# CPU.net
KiCad netlist of a schematic drawn in Altium Designer
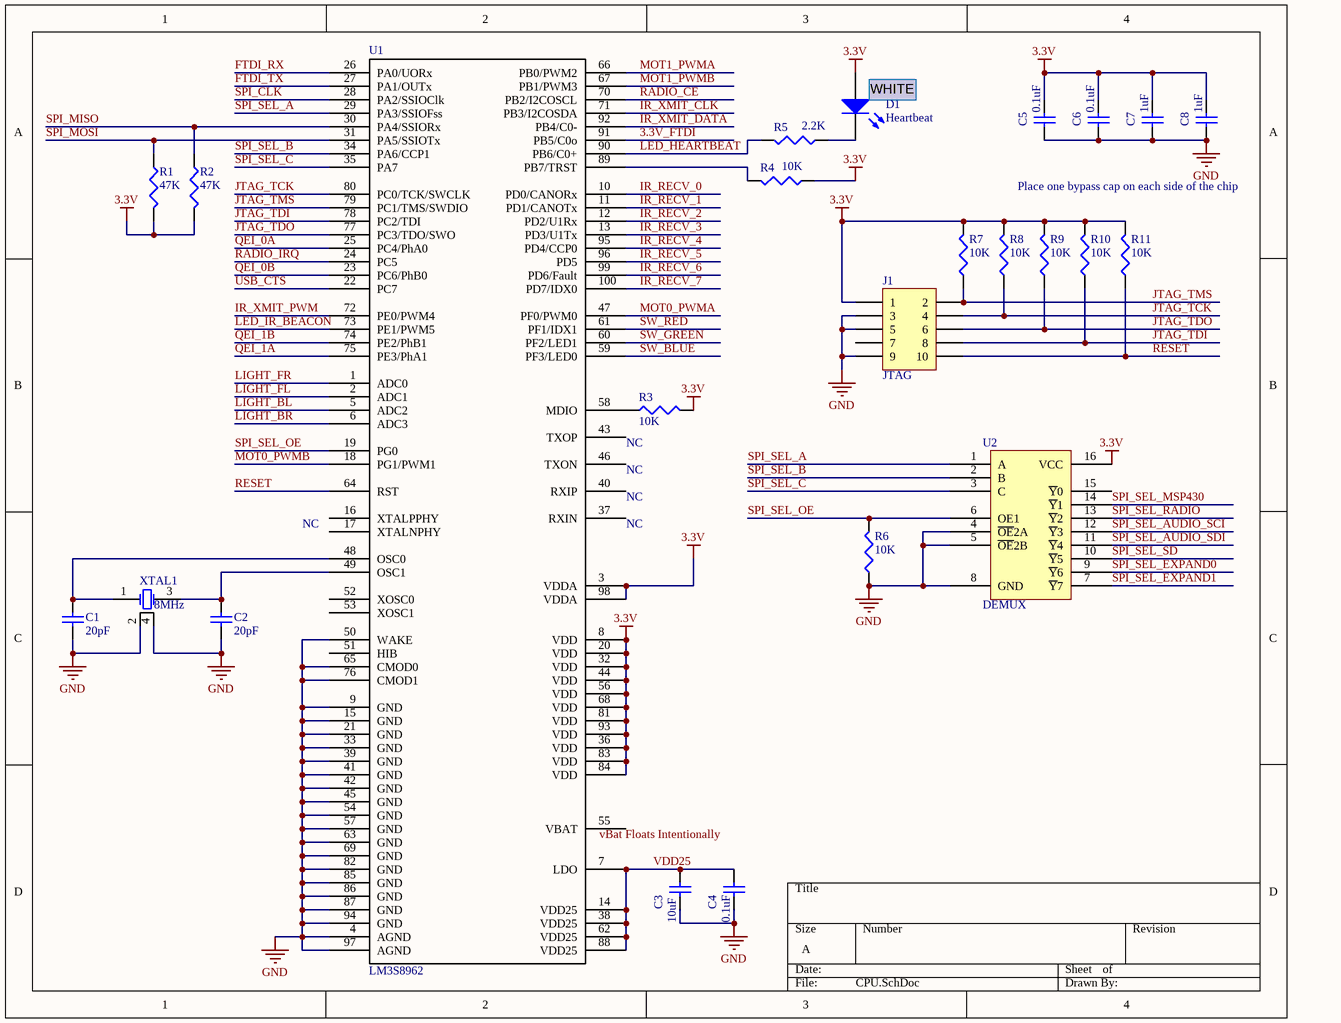
[diagram p0: CPU.SchDoc]

(export (version "E")
  (design (tool "Eeschema 10.0.6"))
  (components
    (comp (ref "C1")
      (value "20pF")
      (footprint "CAPC1005L")
      (description "Capacitor (Semiconductor SIM Model)")
      (fields (field (name "Comment") "Cap Semi") (field (name "PUBLISHER") "Altium Limited"))
      (libsource (lib "Miscellaneous Devices") (part "Cap Semi"))
    )
    (comp (ref "C2")
      (value "20pF")
      (footprint "CAPC1005L")
      (description "Capacitor (Semiconductor SIM Model)")
      (fields (field (name "Comment") "Cap Semi") (field (name "PUBLISHER") "Altium Limited"))
      (libsource (lib "Miscellaneous Devices") (part "Cap Semi"))
    )
    (comp (ref "C3")
      (value "10uF")
      (footprint "CAPC1608L")
      (description "Capacitor (Semiconductor SIM Model)")
      (fields (field (name "Comment") "Cap Semi") (field (name "PUBLISHER") "Altium Limited"))
      (libsource (lib "Miscellaneous Devices") (part "Cap Semi"))
    )
    (comp (ref "C4")
      (value "0.1uF")
      (footprint "CAPC1005L")
      (description "Capacitor (Semiconductor SIM Model)")
      (fields (field (name "Comment") "Cap Semi") (field (name "PUBLISHER") "Altium Limited"))
      (libsource (lib "Miscellaneous Devices") (part "Cap Semi"))
    )
    (comp (ref "C5")
      (value "0.1uF")
      (footprint "CAPC1005L")
      (description "Capacitor (Semiconductor SIM Model)")
      (fields (field (name "Comment") "Cap Semi") (field (name "PUBLISHER") "Altium Limited"))
      (libsource (lib "Miscellaneous Devices") (part "Cap Semi"))
    )
    (comp (ref "C6")
      (value "0.1uF")
      (footprint "CAPC1005L")
      (description "Capacitor (Semiconductor SIM Model)")
      (fields (field (name "Comment") "Cap Semi") (field (name "PUBLISHER") "Altium Limited"))
      (libsource (lib "Miscellaneous Devices") (part "Cap Semi"))
    )
    (comp (ref "C7")
      (value "1uF")
      (footprint "CAPC1608L")
      (description "Capacitor (Semiconductor SIM Model)")
      (fields (field (name "Comment") "Cap Semi") (field (name "PUBLISHER") "Altium Limited"))
      (libsource (lib "Miscellaneous Devices") (part "Cap Semi"))
    )
    (comp (ref "C8")
      (value "1uF")
      (footprint "CAPC1608L")
      (description "Capacitor (Semiconductor SIM Model)")
      (fields (field (name "Comment") "Cap Semi") (field (name "PUBLISHER") "Altium Limited"))
      (libsource (lib "Miscellaneous Devices") (part "Cap Semi"))
    )
    (comp (ref "D1")
      (value "Heartbeat")
      (footprint "SurfaceMount(603)")
      (libsource (lib "mrone") (part "LED"))
    )
    (comp (ref "J1")
      (value "JTAG")
      (footprint "JTAG-10")
      (description "Header, 5-Pin, Dual row, Right Angle")
      (fields (field (name "PUBLISHER") "Altium Limited"))
      (libsource (lib "Miscellaneous Connectors") (part "Header 5X2H"))
    )
    (comp (ref "R1")
      (value "47K")
      (footprint "RESC1608L")
      (description "Resistor")
      (fields (field (name "Comment") "Res3") (field (name "PUBLISHER") "Altium Limited"))
      (libsource (lib "Miscellaneous Devices") (part "Res3"))
    )
    (comp (ref "R2")
      (value "47K")
      (footprint "RESC1608L")
      (description "Resistor")
      (fields (field (name "Comment") "Res3") (field (name "PUBLISHER") "Altium Limited"))
      (libsource (lib "Miscellaneous Devices") (part "Res3"))
    )
    (comp (ref "R3")
      (value "10K")
      (footprint "RESC1608L")
      (description "Resistor")
      (fields (field (name "Comment") "Res3") (field (name "PUBLISHER") "Altium Limited"))
      (libsource (lib "Miscellaneous Devices") (part "Res3"))
    )
    (comp (ref "R4")
      (value "10K")
      (footprint "RESC1608L")
      (description "Resistor")
      (fields (field (name "Comment") "Res3") (field (name "PUBLISHER") "Altium Limited"))
      (libsource (lib "Miscellaneous Devices") (part "Res3"))
    )
    (comp (ref "R5")
      (value "2.2K")
      (footprint "RESC1608L")
      (description "Resistor")
      (fields (field (name "Comment") "Res3") (field (name "PUBLISHER") "Altium Limited"))
      (libsource (lib "Miscellaneous Devices") (part "Res3"))
    )
    (comp (ref "R6")
      (value "10K")
      (footprint "RESC1608L")
      (description "Resistor")
      (fields (field (name "Comment") "Res3") (field (name "PUBLISHER") "Altium Limited"))
      (libsource (lib "Miscellaneous Devices") (part "Res3"))
    )
    (comp (ref "R7")
      (value "10K")
      (footprint "RESC1608L")
      (description "Resistor")
      (fields (field (name "Comment") "Res3") (field (name "PUBLISHER") "Altium Limited"))
      (libsource (lib "Miscellaneous Devices") (part "Res3"))
    )
    (comp (ref "R8")
      (value "10K")
      (footprint "RESC1608L")
      (description "Resistor")
      (fields (field (name "Comment") "Res3") (field (name "PUBLISHER") "Altium Limited"))
      (libsource (lib "Miscellaneous Devices") (part "Res3"))
    )
    (comp (ref "R9")
      (value "10K")
      (footprint "RESC1608L")
      (description "Resistor")
      (fields (field (name "Comment") "Res3") (field (name "PUBLISHER") "Altium Limited"))
      (libsource (lib "Miscellaneous Devices") (part "Res3"))
    )
    (comp (ref "R10")
      (value "10K")
      (footprint "RESC1608L")
      (description "Resistor")
      (fields (field (name "Comment") "Res3") (field (name "PUBLISHER") "Altium Limited"))
      (libsource (lib "Miscellaneous Devices") (part "Res3"))
    )
    (comp (ref "R11")
      (value "10K")
      (footprint "RESC1608L")
      (description "Resistor")
      (fields (field (name "Comment") "Res3") (field (name "PUBLISHER") "Altium Limited"))
      (libsource (lib "Miscellaneous Devices") (part "Res3"))
    )
    (comp (ref "U1")
      (value "LM3S8962")
      (footprint "LQFP-100")
      (libsource (lib "Schematic Components") (part "LM3S8962"))
    )
    (comp (ref "U2") (value "DEMUX") (footprint "TSSOP-16") (libsource (lib "mrone") (part "DEMUX")))
    (comp (ref "XTAL1") (value "8MHz") (footprint "CRYSTAL") (libsource (lib "mrone") (part "Crystal")))
  )
  (nets
    (net (code "1") (name "/3.3V_FTDI") (class "Default")
      (node (ref "U1") (pin "91") (pinfunction "PB5/C0o_91") (pintype "passive"))
    )
    (net (code "2") (name "/FTDI_RX") (class "Default")
      (node (ref "U1") (pin "26") (pinfunction "PA0/UORx_26") (pintype "passive"))
    )
    (net (code "3") (name "/FTDI_TX") (class "Default")
      (node (ref "U1") (pin "27") (pinfunction "PA1/OUTx_27") (pintype "passive"))
    )
    (net (code "4") (name "/IR_RECV_0") (class "Default")
      (node (ref "U1") (pin "10") (pinfunction "PD0/CANORx_10") (pintype "passive"))
    )
    (net (code "5") (name "/IR_RECV_1") (class "Default")
      (node (ref "U1") (pin "11") (pinfunction "PD1/CANOTx_11") (pintype "passive"))
    )
    (net (code "6") (name "/IR_RECV_2") (class "Default")
      (node (ref "U1") (pin "12") (pinfunction "PD2/U1Rx_12") (pintype "passive"))
    )
    (net (code "7") (name "/IR_RECV_3") (class "Default")
      (node (ref "U1") (pin "13") (pinfunction "PD3/U1Tx_13") (pintype "passive"))
    )
    (net (code "8") (name "/IR_RECV_4") (class "Default")
      (node (ref "U1") (pin "95") (pinfunction "PD4/CCP0_95") (pintype "passive"))
    )
    (net (code "9") (name "/IR_RECV_5") (class "Default")
      (node (ref "U1") (pin "96") (pinfunction "PD5_96") (pintype "passive"))
    )
    (net (code "10") (name "/IR_RECV_6") (class "Default")
      (node (ref "U1") (pin "99") (pinfunction "PD6/Fault_99") (pintype "passive"))
    )
    (net (code "11") (name "/IR_RECV_7") (class "Default")
      (node (ref "U1") (pin "100") (pinfunction "PD7/IDX0_100") (pintype "passive"))
    )
    (net (code "12") (name "/IR_XMIT_CLK") (class "Default")
      (node (ref "U1") (pin "71") (pinfunction "PB3/I2COSDA_71") (pintype "passive"))
    )
    (net (code "13") (name "/IR_XMIT_DATA") (class "Default")
      (node (ref "U1") (pin "92") (pinfunction "PB4/C0-_92") (pintype "passive"))
    )
    (net (code "14") (name "/IR_XMIT_PWM") (class "Default")
      (node (ref "U1") (pin "72") (pinfunction "PE0/PWM4_72") (pintype "passive"))
    )
    (net (code "15") (name "/JTAG_TCK") (class "Default")
      (node (ref "J1") (pin "4") (pinfunction "4_4") (pintype "passive"))
      (node (ref "R8") (pin "1") (pinfunction "1_1") (pintype "passive"))
      (node (ref "U1") (pin "80") (pinfunction "PC0/TCK/SWCLK_80") (pintype "passive"))
    )
    (net (code "16") (name "/JTAG_TDI") (class "Default")
      (node (ref "J1") (pin "8") (pinfunction "8_8") (pintype "passive"))
      (node (ref "R10") (pin "1") (pinfunction "1_1") (pintype "passive"))
      (node (ref "U1") (pin "78") (pinfunction "PC2/TDI_78") (pintype "passive"))
    )
    (net (code "17") (name "/JTAG_TDO") (class "Default")
      (node (ref "J1") (pin "6") (pinfunction "6_6") (pintype "passive"))
      (node (ref "R9") (pin "1") (pinfunction "1_1") (pintype "passive"))
      (node (ref "U1") (pin "77") (pinfunction "PC3/TDO/SWO_77") (pintype "passive"))
    )
    (net (code "18") (name "/JTAG_TMS") (class "Default")
      (node (ref "J1") (pin "2") (pinfunction "2_2") (pintype "passive"))
      (node (ref "R7") (pin "1") (pinfunction "1_1") (pintype "passive"))
      (node (ref "U1") (pin "79") (pinfunction "PC1/TMS/SWDIO_79") (pintype "passive"))
    )
    (net (code "19") (name "/LED_HEARTBEAT") (class "Default")
      (node (ref "R5") (pin "2") (pinfunction "2_2") (pintype "passive"))
      (node (ref "U1") (pin "90") (pinfunction "PB6/C0+_90") (pintype "passive"))
    )
    (net (code "20") (name "/LED_IR_BEACON") (class "Default")
      (node (ref "U1") (pin "73") (pinfunction "PE1/PWM5_73") (pintype "passive"))
    )
    (net (code "21") (name "/LIGHT_BL") (class "Default")
      (node (ref "U1") (pin "5") (pinfunction "ADC2_5") (pintype "passive"))
    )
    (net (code "22") (name "/LIGHT_BR") (class "Default")
      (node (ref "U1") (pin "6") (pinfunction "ADC3_6") (pintype "passive"))
    )
    (net (code "23") (name "/LIGHT_FL") (class "Default")
      (node (ref "U1") (pin "2") (pinfunction "ADC1_2") (pintype "passive"))
    )
    (net (code "24") (name "/LIGHT_FR") (class "Default")
      (node (ref "U1") (pin "1") (pinfunction "ADC0_1") (pintype "passive"))
    )
    (net (code "25") (name "/MOT0_PWMA") (class "Default")
      (node (ref "U1") (pin "47") (pinfunction "PF0/PWM0_47") (pintype "passive"))
    )
    (net (code "26") (name "/MOT0_PWMB") (class "Default")
      (node (ref "U1") (pin "18") (pinfunction "PG1/PWM1_18") (pintype "passive"))
    )
    (net (code "27") (name "/MOT1_PWMA") (class "Default")
      (node (ref "U1") (pin "66") (pinfunction "PB0/PWM2_66") (pintype "passive"))
    )
    (net (code "28") (name "/MOT1_PWMB") (class "Default")
      (node (ref "U1") (pin "67") (pinfunction "PB1/PWM3_67") (pintype "passive"))
    )
    (net (code "29") (name "/QEI_0A") (class "Default")
      (node (ref "U1") (pin "25") (pinfunction "PC4/PhA0_25") (pintype "passive"))
    )
    (net (code "30") (name "/QEI_0B") (class "Default")
      (node (ref "U1") (pin "23") (pinfunction "PC6/PhB0_23") (pintype "passive"))
    )
    (net (code "31") (name "/QEI_1A") (class "Default")
      (node (ref "U1") (pin "75") (pinfunction "PE3/PhA1_75") (pintype "passive"))
    )
    (net (code "32") (name "/QEI_1B") (class "Default")
      (node (ref "U1") (pin "74") (pinfunction "PE2/PhB1_74") (pintype "passive"))
    )
    (net (code "33") (name "/RADIO_CE") (class "Default")
      (node (ref "U1") (pin "70") (pinfunction "PB2/I2COSCL_70") (pintype "passive"))
    )
    (net (code "34") (name "/RADIO_IRQ") (class "Default")
      (node (ref "U1") (pin "24") (pinfunction "PC5_24") (pintype "passive"))
    )
    (net (code "35") (name "/RESET") (class "Default")
      (node (ref "J1") (pin "10") (pinfunction "10_10") (pintype "passive"))
      (node (ref "R11") (pin "1") (pinfunction "1_1") (pintype "passive"))
      (node (ref "U1") (pin "64") (pinfunction "RST_64") (pintype "passive"))
    )
    (net (code "36") (name "/SPI_CLK") (class "Default")
      (node (ref "U1") (pin "28") (pinfunction "PA2/SSIOClk_28") (pintype "passive"))
    )
    (net (code "37") (name "/SPI_MISO") (class "Default")
      (node (ref "R2") (pin "1") (pinfunction "1_1") (pintype "passive"))
      (node (ref "U1") (pin "30") (pinfunction "PA4/SSIORx_30") (pintype "passive"))
    )
    (net (code "38") (name "/SPI_MOSI") (class "Default")
      (node (ref "R1") (pin "1") (pinfunction "1_1") (pintype "passive"))
      (node (ref "U1") (pin "31") (pinfunction "PA5/SSIOTx_31") (pintype "passive"))
    )
    (net (code "39") (name "/SPI_SEL_A") (class "Default")
      (node (ref "U1") (pin "29") (pinfunction "PA3/SSIOFss_29") (pintype "passive"))
      (node (ref "U2") (pin "1") (pinfunction "A_1") (pintype "passive"))
    )
    (net (code "40") (name "/SPI_SEL_AUDIO_SCI") (class "Default")
      (node (ref "U2") (pin "12") (pinfunction "~{Y}3_12") (pintype "passive"))
    )
    (net (code "41") (name "/SPI_SEL_AUDIO_SDI") (class "Default")
      (node (ref "U2") (pin "11") (pinfunction "~{Y}4_11") (pintype "passive"))
    )
    (net (code "42") (name "/SPI_SEL_B") (class "Default")
      (node (ref "U1") (pin "34") (pinfunction "PA6/CCP1_34") (pintype "passive"))
      (node (ref "U2") (pin "2") (pinfunction "B_2") (pintype "passive"))
    )
    (net (code "43") (name "/SPI_SEL_C") (class "Default")
      (node (ref "U1") (pin "35") (pinfunction "PA7_35") (pintype "passive"))
      (node (ref "U2") (pin "3") (pinfunction "C_3") (pintype "passive"))
    )
    (net (code "44") (name "/SPI_SEL_EXPAND0") (class "Default")
      (node (ref "U2") (pin "9") (pinfunction "~{Y}6_9") (pintype "passive"))
    )
    (net (code "45") (name "/SPI_SEL_EXPAND1") (class "Default")
      (node (ref "U2") (pin "7") (pinfunction "~{Y}7_7") (pintype "passive"))
    )
    (net (code "46") (name "/SPI_SEL_MSP430") (class "Default")
      (node (ref "U2") (pin "14") (pinfunction "~{Y}1_14") (pintype "passive"))
    )
    (net (code "47") (name "/SPI_SEL_OE") (class "Default")
      (node (ref "R6") (pin "2") (pinfunction "2_2") (pintype "passive"))
      (node (ref "U1") (pin "19") (pinfunction "PG0_19") (pintype "passive"))
      (node (ref "U2") (pin "6") (pinfunction "OE1_6") (pintype "passive"))
    )
    (net (code "48") (name "/SPI_SEL_RADIO") (class "Default")
      (node (ref "U2") (pin "13") (pinfunction "~{Y}2_13") (pintype "passive"))
    )
    (net (code "49") (name "/SPI_SEL_SD") (class "Default")
      (node (ref "U2") (pin "10") (pinfunction "~{Y}5_10") (pintype "passive"))
    )
    (net (code "50") (name "/SW_BLUE") (class "Default")
      (node (ref "U1") (pin "59") (pinfunction "PF3/LED0_59") (pintype "passive"))
    )
    (net (code "51") (name "/SW_GREEN") (class "Default")
      (node (ref "U1") (pin "60") (pinfunction "PF2/LED1_60") (pintype "passive"))
    )
    (net (code "52") (name "/SW_RED") (class "Default")
      (node (ref "U1") (pin "61") (pinfunction "PF1/IDX1_61") (pintype "passive"))
    )
    (net (code "53") (name "/USB_CTS") (class "Default")
      (node (ref "U1") (pin "22") (pinfunction "PC7_22") (pintype "passive"))
    )
    (net (code "54") (name "/VDD25") (class "Default")
      (node (ref "C3") (pin "2") (pinfunction "2_2") (pintype "passive"))
      (node (ref "C4") (pin "2") (pinfunction "2_2") (pintype "passive"))
      (node (ref "U1") (pin "14") (pinfunction "VDD25_14") (pintype "passive"))
      (node (ref "U1") (pin "38") (pinfunction "VDD25_38") (pintype "passive"))
      (node (ref "U1") (pin "62") (pinfunction "VDD25_62") (pintype "passive"))
      (node (ref "U1") (pin "7") (pinfunction "LDO_7") (pintype "passive"))
      (node (ref "U1") (pin "88") (pinfunction "VDD25_88") (pintype "passive"))
    )
    (net (code "55") (name "3.3V") (class "Default")
      (node (ref "C5") (pin "2") (pinfunction "2_2") (pintype "passive"))
      (node (ref "C6") (pin "2") (pinfunction "2_2") (pintype "passive"))
      (node (ref "C7") (pin "2") (pinfunction "2_2") (pintype "passive"))
      (node (ref "C8") (pin "2") (pinfunction "2_2") (pintype "passive"))
      (node (ref "D1") (pin "1") (pinfunction "A_1") (pintype "passive"))
      (node (ref "J1") (pin "1") (pinfunction "1_1") (pintype "passive"))
      (node (ref "R1") (pin "2") (pinfunction "2_2") (pintype "passive"))
      (node (ref "R10") (pin "2") (pinfunction "2_2") (pintype "passive"))
      (node (ref "R11") (pin "2") (pinfunction "2_2") (pintype "passive"))
      (node (ref "R2") (pin "2") (pinfunction "2_2") (pintype "passive"))
      (node (ref "R3") (pin "2") (pinfunction "2_2") (pintype "passive"))
      (node (ref "R4") (pin "1") (pinfunction "1_1") (pintype "passive"))
      (node (ref "R7") (pin "2") (pinfunction "2_2") (pintype "passive"))
      (node (ref "R8") (pin "2") (pinfunction "2_2") (pintype "passive"))
      (node (ref "R9") (pin "2") (pinfunction "2_2") (pintype "passive"))
      (node (ref "U1") (pin "20") (pinfunction "VDD_20") (pintype "passive"))
      (node (ref "U1") (pin "3") (pinfunction "VDDA_3") (pintype "passive"))
      (node (ref "U1") (pin "32") (pinfunction "VDD_32") (pintype "passive"))
      (node (ref "U1") (pin "36") (pinfunction "VDD_36") (pintype "passive"))
      (node (ref "U1") (pin "44") (pinfunction "VDD_44") (pintype "passive"))
      (node (ref "U1") (pin "56") (pinfunction "VDD_56") (pintype "passive"))
      (node (ref "U1") (pin "68") (pinfunction "VDD_68") (pintype "passive"))
      (node (ref "U1") (pin "8") (pinfunction "VDD_8") (pintype "passive"))
      (node (ref "U1") (pin "81") (pinfunction "VDD_81") (pintype "passive"))
      (node (ref "U1") (pin "83") (pinfunction "VDD_83") (pintype "passive"))
      (node (ref "U1") (pin "84") (pinfunction "VDD_84") (pintype "passive"))
      (node (ref "U1") (pin "93") (pinfunction "VDD_93") (pintype "passive"))
      (node (ref "U1") (pin "98") (pinfunction "VDDA_98") (pintype "passive"))
      (node (ref "U2") (pin "16") (pinfunction "VCC_16") (pintype "passive"))
    )
    (net (code "56") (name "GND") (class "Default")
      (node (ref "C1") (pin "1") (pinfunction "1_1") (pintype "passive"))
      (node (ref "C2") (pin "1") (pinfunction "1_1") (pintype "passive"))
      (node (ref "C3") (pin "1") (pinfunction "1_1") (pintype "passive"))
      (node (ref "C4") (pin "1") (pinfunction "1_1") (pintype "passive"))
      (node (ref "C5") (pin "1") (pinfunction "1_1") (pintype "passive"))
      (node (ref "C6") (pin "1") (pinfunction "1_1") (pintype "passive"))
      (node (ref "C7") (pin "1") (pinfunction "1_1") (pintype "passive"))
      (node (ref "C8") (pin "1") (pinfunction "1_1") (pintype "passive"))
      (node (ref "J1") (pin "3") (pinfunction "3_3") (pintype "passive"))
      (node (ref "J1") (pin "5") (pinfunction "5_5") (pintype "passive"))
      (node (ref "J1") (pin "9") (pinfunction "9_9") (pintype "passive"))
      (node (ref "R6") (pin "1") (pinfunction "1_1") (pintype "passive"))
      (node (ref "U1") (pin "15") (pinfunction "GND_15") (pintype "passive"))
      (node (ref "U1") (pin "21") (pinfunction "GND_21") (pintype "passive"))
      (node (ref "U1") (pin "33") (pinfunction "GND_33") (pintype "passive"))
      (node (ref "U1") (pin "39") (pinfunction "GND_39") (pintype "passive"))
      (node (ref "U1") (pin "4") (pinfunction "AGND_4") (pintype "passive"))
      (node (ref "U1") (pin "41") (pinfunction "GND_41") (pintype "passive"))
      (node (ref "U1") (pin "42") (pinfunction "GND_42") (pintype "passive"))
      (node (ref "U1") (pin "45") (pinfunction "GND_45") (pintype "passive"))
      (node (ref "U1") (pin "50") (pinfunction "WAKE_50") (pintype "passive"))
      (node (ref "U1") (pin "54") (pinfunction "GND_54") (pintype "passive"))
      (node (ref "U1") (pin "57") (pinfunction "GND_57") (pintype "passive"))
      (node (ref "U1") (pin "63") (pinfunction "GND_63") (pintype "passive"))
      (node (ref "U1") (pin "65") (pinfunction "CMOD0_65") (pintype "passive"))
      (node (ref "U1") (pin "69") (pinfunction "GND_69") (pintype "passive"))
      (node (ref "U1") (pin "76") (pinfunction "CMOD1_76") (pintype "passive"))
      (node (ref "U1") (pin "82") (pinfunction "GND_82") (pintype "passive"))
      (node (ref "U1") (pin "85") (pinfunction "GND_85") (pintype "passive"))
      (node (ref "U1") (pin "86") (pinfunction "GND_86") (pintype "passive"))
      (node (ref "U1") (pin "87") (pinfunction "GND_87") (pintype "passive"))
      (node (ref "U1") (pin "9") (pinfunction "GND_9") (pintype "passive"))
      (node (ref "U1") (pin "94") (pinfunction "GND_94") (pintype "passive"))
      (node (ref "U1") (pin "97") (pinfunction "AGND_97") (pintype "passive"))
      (node (ref "U2") (pin "4") (pinfunction "~{OE}2A_4") (pintype "passive"))
      (node (ref "U2") (pin "5") (pinfunction "~{OE}2B_5") (pintype "passive"))
      (node (ref "U2") (pin "8") (pinfunction "GND_8") (pintype "passive"))
      (node (ref "XTAL1") (pin "2") (pinfunction "GND_2") (pintype "passive"))
      (node (ref "XTAL1") (pin "4") (pinfunction "GND_4") (pintype "passive"))
    )
    (net (code "57") (name "Net-(D1-K)") (class "Default")
      (node (ref "D1") (pin "2") (pinfunction "K_2") (pintype "passive"))
      (node (ref "R5") (pin "1") (pinfunction "1_1") (pintype "passive"))
    )
    (net (code "58") (name "Net-(U1-MDIO)") (class "Default")
      (node (ref "R3") (pin "1") (pinfunction "1_1") (pintype "passive"))
      (node (ref "U1") (pin "58") (pinfunction "MDIO_58") (pintype "passive"))
    )
    (net (code "59") (name "Net-(U1-OSC0)") (class "Default")
      (node (ref "C1") (pin "2") (pinfunction "2_2") (pintype "passive"))
      (node (ref "U1") (pin "48") (pinfunction "OSC0_48") (pintype "passive"))
      (node (ref "XTAL1") (pin "1") (pinfunction "OSC1_1") (pintype "passive"))
    )
    (net (code "60") (name "Net-(U1-OSC1)") (class "Default")
      (node (ref "C2") (pin "2") (pinfunction "2_2") (pintype "passive"))
      (node (ref "U1") (pin "49") (pinfunction "OSC1_49") (pintype "passive"))
      (node (ref "XTAL1") (pin "3") (pinfunction "OSC2_3") (pintype "passive"))
    )
    (net (code "61") (name "Net-(U1-PB7{slash}TRST)") (class "Default")
      (node (ref "R4") (pin "2") (pinfunction "2_2") (pintype "passive"))
      (node (ref "U1") (pin "89") (pinfunction "PB7/TRST_89") (pintype "passive"))
    )
    (net (code "62") (name "unconnected-(J1-Pad7)") (class "Default")
      (node (ref "J1") (pin "7") (pinfunction "7_7") (pintype "passive"))
    )
    (net (code "63") (name "unconnected-(U1-HIB-Pad51)") (class "Default")
      (node (ref "U1") (pin "51") (pinfunction "HIB_51") (pintype "passive"))
    )
    (net (code "64") (name "unconnected-(U1-RXIN-Pad37)") (class "Default")
      (node (ref "U1") (pin "37") (pinfunction "RXIN_37") (pintype "passive"))
    )
    (net (code "65") (name "unconnected-(U1-RXIP-Pad40)") (class "Default")
      (node (ref "U1") (pin "40") (pinfunction "RXIP_40") (pintype "passive"))
    )
    (net (code "66") (name "unconnected-(U1-TXON-Pad46)") (class "Default")
      (node (ref "U1") (pin "46") (pinfunction "TXON_46") (pintype "passive"))
    )
    (net (code "67") (name "unconnected-(U1-TXOP-Pad43)") (class "Default")
      (node (ref "U1") (pin "43") (pinfunction "TXOP_43") (pintype "passive"))
    )
    (net (code "68") (name "unconnected-(U1-VBAT-Pad55)") (class "Default")
      (node (ref "U1") (pin "55") (pinfunction "VBAT_55") (pintype "passive"))
    )
    (net (code "69") (name "unconnected-(U1-XOSC0-Pad52)") (class "Default")
      (node (ref "U1") (pin "52") (pinfunction "XOSC0_52") (pintype "passive"))
    )
    (net (code "70") (name "unconnected-(U1-XOSC1-Pad53)") (class "Default")
      (node (ref "U1") (pin "53") (pinfunction "XOSC1_53") (pintype "passive"))
    )
    (net (code "71") (name "unconnected-(U1-XTALNPHY-Pad17)") (class "Default")
      (node (ref "U1") (pin "17") (pinfunction "XTALNPHY_17") (pintype "passive"))
    )
    (net (code "72") (name "unconnected-(U1-XTALPPHY-Pad16)") (class "Default")
      (node (ref "U1") (pin "16") (pinfunction "XTALPPHY_16") (pintype "passive"))
    )
    (net (code "73") (name "unconnected-(U2-~{Y}0-Pad15)") (class "Default")
      (node (ref "U2") (pin "15") (pinfunction "~{Y}0_15") (pintype "passive"))
    )
  )
)
